# Digital_Port_C_Button.net
KiCad netlist of a schematic drawn in Altium Designer
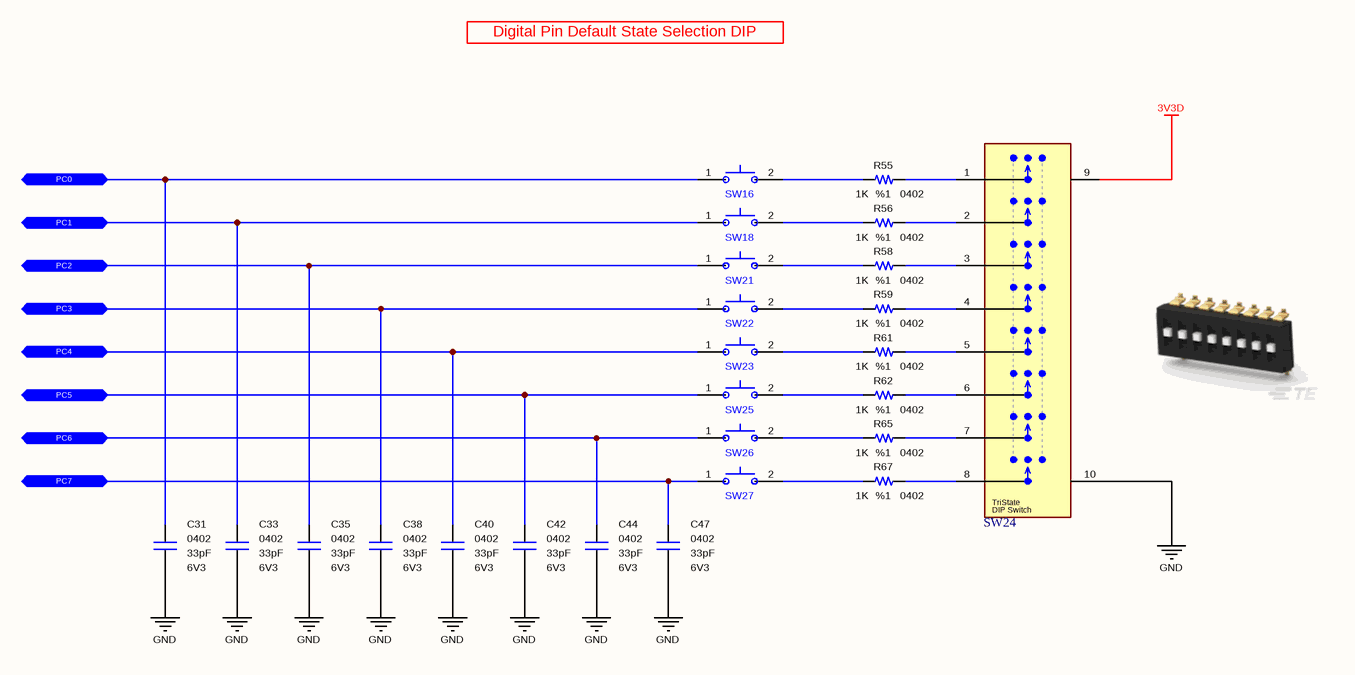
[diagram p0: Digital Port C Button.SchDoc]

(export (version "E")
  (design (tool "Eeschema 10.0.6"))
  (components
    (comp (ref "C31")
      (value "33pF")
      (footprint "CAPACITOR_0402")
      (description "Capacitor - 33pF [0402] (Ceramic)")
      (fields
        (field (name "MANUFACTURER PART NUMBER") "C0402C330J9RACAUTO")
        (field (name "MOUSER PART NUMBER") "80-C0402C330J9RAUTO")
        (field (name "CASE") "0402")
        (field (name "VOLTAGE") "6V3")
      )
      (libsource (lib "Ovoo_Library") (part "Capacitor - 33pF [0402-6V3]"))
    )
    (comp (ref "C33")
      (value "33pF")
      (footprint "CAPACITOR_0402")
      (description "Capacitor - 33pF [0402] (Ceramic)")
      (fields
        (field (name "MANUFACTURER PART NUMBER") "C0402C330J9RACAUTO")
        (field (name "MOUSER PART NUMBER") "80-C0402C330J9RAUTO")
        (field (name "CASE") "0402")
        (field (name "VOLTAGE") "6V3")
      )
      (libsource (lib "Ovoo_Library") (part "Capacitor - 33pF [0402-6V3]"))
    )
    (comp (ref "C35")
      (value "33pF")
      (footprint "CAPACITOR_0402")
      (description "Capacitor - 33pF [0402] (Ceramic)")
      (fields
        (field (name "MANUFACTURER PART NUMBER") "C0402C330J9RACAUTO")
        (field (name "MOUSER PART NUMBER") "80-C0402C330J9RAUTO")
        (field (name "CASE") "0402")
        (field (name "VOLTAGE") "6V3")
      )
      (libsource (lib "Ovoo_Library") (part "Capacitor - 33pF [0402-6V3]"))
    )
    (comp (ref "C38")
      (value "33pF")
      (footprint "CAPACITOR_0402")
      (description "Capacitor - 33pF [0402] (Ceramic)")
      (fields
        (field (name "MANUFACTURER PART NUMBER") "C0402C330J9RACAUTO")
        (field (name "MOUSER PART NUMBER") "80-C0402C330J9RAUTO")
        (field (name "CASE") "0402")
        (field (name "VOLTAGE") "6V3")
      )
      (libsource (lib "Ovoo_Library") (part "Capacitor - 33pF [0402-6V3]"))
    )
    (comp (ref "C40")
      (value "33pF")
      (footprint "CAPACITOR_0402")
      (description "Capacitor - 33pF [0402] (Ceramic)")
      (fields
        (field (name "MANUFACTURER PART NUMBER") "C0402C330J9RACAUTO")
        (field (name "MOUSER PART NUMBER") "80-C0402C330J9RAUTO")
        (field (name "CASE") "0402")
        (field (name "VOLTAGE") "6V3")
      )
      (libsource (lib "Ovoo_Library") (part "Capacitor - 33pF [0402-6V3]"))
    )
    (comp (ref "C42")
      (value "33pF")
      (footprint "CAPACITOR_0402")
      (description "Capacitor - 33pF [0402] (Ceramic)")
      (fields
        (field (name "MANUFACTURER PART NUMBER") "C0402C330J9RACAUTO")
        (field (name "MOUSER PART NUMBER") "80-C0402C330J9RAUTO")
        (field (name "CASE") "0402")
        (field (name "VOLTAGE") "6V3")
      )
      (libsource (lib "Ovoo_Library") (part "Capacitor - 33pF [0402-6V3]"))
    )
    (comp (ref "C44")
      (value "33pF")
      (footprint "CAPACITOR_0402")
      (description "Capacitor - 33pF [0402] (Ceramic)")
      (fields
        (field (name "MANUFACTURER PART NUMBER") "C0402C330J9RACAUTO")
        (field (name "MOUSER PART NUMBER") "80-C0402C330J9RAUTO")
        (field (name "CASE") "0402")
        (field (name "VOLTAGE") "6V3")
      )
      (libsource (lib "Ovoo_Library") (part "Capacitor - 33pF [0402-6V3]"))
    )
    (comp (ref "C47")
      (value "33pF")
      (footprint "CAPACITOR_0402")
      (description "Capacitor - 33pF [0402] (Ceramic)")
      (fields
        (field (name "MANUFACTURER PART NUMBER") "C0402C330J9RACAUTO")
        (field (name "MOUSER PART NUMBER") "80-C0402C330J9RAUTO")
        (field (name "CASE") "0402")
        (field (name "VOLTAGE") "6V3")
      )
      (libsource (lib "Ovoo_Library") (part "Capacitor - 33pF [0402-6V3]"))
    )
    (comp (ref "R55")
      (value "1K")
      (footprint "RESISTOR_0402")
      (description "Thick Film Resistors - SMD 1/16 W 1.0 Kohms 1%")
      (fields
        (field (name "MANUFACTURER PART NUMBER") "CRCW04021K00FKED")
        (field (name "MOUSER PART NUMBER") "71-CRCW0402-1.0K-E3")
        (field (name "TOLERANCE") "%1")
        (field (name "CASE") "0402")
      )
      (libsource (lib "Ovoo_Library") (part "Resistor - 1K"))
    )
    (comp (ref "R56")
      (value "1K")
      (footprint "RESISTOR_0402")
      (description "Thick Film Resistors - SMD 1/16 W 1.0 Kohms 1%")
      (fields
        (field (name "MANUFACTURER PART NUMBER") "CRCW04021K00FKED")
        (field (name "MOUSER PART NUMBER") "71-CRCW0402-1.0K-E3")
        (field (name "TOLERANCE") "%1")
        (field (name "CASE") "0402")
      )
      (libsource (lib "Ovoo_Library") (part "Resistor - 1K"))
    )
    (comp (ref "R58")
      (value "1K")
      (footprint "RESISTOR_0402")
      (description "Thick Film Resistors - SMD 1/16 W 1.0 Kohms 1%")
      (fields
        (field (name "MANUFACTURER PART NUMBER") "CRCW04021K00FKED")
        (field (name "MOUSER PART NUMBER") "71-CRCW0402-1.0K-E3")
        (field (name "TOLERANCE") "%1")
        (field (name "CASE") "0402")
      )
      (libsource (lib "Ovoo_Library") (part "Resistor - 1K"))
    )
    (comp (ref "R59")
      (value "1K")
      (footprint "RESISTOR_0402")
      (description "Thick Film Resistors - SMD 1/16 W 1.0 Kohms 1%")
      (fields
        (field (name "MANUFACTURER PART NUMBER") "CRCW04021K00FKED")
        (field (name "MOUSER PART NUMBER") "71-CRCW0402-1.0K-E3")
        (field (name "TOLERANCE") "%1")
        (field (name "CASE") "0402")
      )
      (libsource (lib "Ovoo_Library") (part "Resistor - 1K"))
    )
    (comp (ref "R61")
      (value "1K")
      (footprint "RESISTOR_0402")
      (description "Thick Film Resistors - SMD 1/16 W 1.0 Kohms 1%")
      (fields
        (field (name "MANUFACTURER PART NUMBER") "CRCW04021K00FKED")
        (field (name "MOUSER PART NUMBER") "71-CRCW0402-1.0K-E3")
        (field (name "TOLERANCE") "%1")
        (field (name "CASE") "0402")
      )
      (libsource (lib "Ovoo_Library") (part "Resistor - 1K"))
    )
    (comp (ref "R62")
      (value "1K")
      (footprint "RESISTOR_0402")
      (description "Thick Film Resistors - SMD 1/16 W 1.0 Kohms 1%")
      (fields
        (field (name "MANUFACTURER PART NUMBER") "CRCW04021K00FKED")
        (field (name "MOUSER PART NUMBER") "71-CRCW0402-1.0K-E3")
        (field (name "TOLERANCE") "%1")
        (field (name "CASE") "0402")
      )
      (libsource (lib "Ovoo_Library") (part "Resistor - 1K"))
    )
    (comp (ref "R65")
      (value "1K")
      (footprint "RESISTOR_0402")
      (description "Thick Film Resistors - SMD 1/16 W 1.0 Kohms 1%")
      (fields
        (field (name "MANUFACTURER PART NUMBER") "CRCW04021K00FKED")
        (field (name "MOUSER PART NUMBER") "71-CRCW0402-1.0K-E3")
        (field (name "TOLERANCE") "%1")
        (field (name "CASE") "0402")
      )
      (libsource (lib "Ovoo_Library") (part "Resistor - 1K"))
    )
    (comp (ref "R67")
      (value "1K")
      (footprint "RESISTOR_0402")
      (description "Thick Film Resistors - SMD 1/16 W 1.0 Kohms 1%")
      (fields
        (field (name "MANUFACTURER PART NUMBER") "CRCW04021K00FKED")
        (field (name "MOUSER PART NUMBER") "71-CRCW0402-1.0K-E3")
        (field (name "TOLERANCE") "%1")
        (field (name "CASE") "0402")
      )
      (libsource (lib "Ovoo_Library") (part "Resistor - 1K"))
    )
    (comp (ref "SW16")
      (value "Tactile Switches")
      (footprint "PTS526_Switch")
      (description "Tactile Switches 50mA 12VDC, 5.2x5.2mm, 0.8mm H, 260gf, G leads.")
      (fields
        (field (name "MANUFACTURER PART NUMBER") "PTS526 SK08 SMTR2 LFS")
        (field (name "MOUSER PART NUMBER") "611-PTS526SK08SMTR2L")
      )
      (libsource (lib "Ovoo_Library") (part "Switch - Tactile"))
    )
    (comp (ref "SW18")
      (value "Tactile Switches")
      (footprint "PTS526_Switch")
      (description "Tactile Switches 50mA 12VDC, 5.2x5.2mm, 0.8mm H, 260gf, G leads.")
      (fields
        (field (name "MANUFACTURER PART NUMBER") "PTS526 SK08 SMTR2 LFS")
        (field (name "MOUSER PART NUMBER") "611-PTS526SK08SMTR2L")
      )
      (libsource (lib "Ovoo_Library") (part "Switch - Tactile"))
    )
    (comp (ref "SW21")
      (value "Tactile Switches")
      (footprint "PTS526_Switch")
      (description "Tactile Switches 50mA 12VDC, 5.2x5.2mm, 0.8mm H, 260gf, G leads.")
      (fields
        (field (name "MANUFACTURER PART NUMBER") "PTS526 SK08 SMTR2 LFS")
        (field (name "MOUSER PART NUMBER") "611-PTS526SK08SMTR2L")
      )
      (libsource (lib "Ovoo_Library") (part "Switch - Tactile"))
    )
    (comp (ref "SW22")
      (value "Tactile Switches")
      (footprint "PTS526_Switch")
      (description "Tactile Switches 50mA 12VDC, 5.2x5.2mm, 0.8mm H, 260gf, G leads.")
      (fields
        (field (name "MANUFACTURER PART NUMBER") "PTS526 SK08 SMTR2 LFS")
        (field (name "MOUSER PART NUMBER") "611-PTS526SK08SMTR2L")
      )
      (libsource (lib "Ovoo_Library") (part "Switch - Tactile"))
    )
    (comp (ref "SW23")
      (value "Tactile Switches")
      (footprint "PTS526_Switch")
      (description "Tactile Switches 50mA 12VDC, 5.2x5.2mm, 0.8mm H, 260gf, G leads.")
      (fields
        (field (name "MANUFACTURER PART NUMBER") "PTS526 SK08 SMTR2 LFS")
        (field (name "MOUSER PART NUMBER") "611-PTS526SK08SMTR2L")
      )
      (libsource (lib "Ovoo_Library") (part "Switch - Tactile"))
    )
    (comp (ref "SW24")
      (value "DIP Switches/SIP Switches")
      (footprint "TDS08SGNNTR04")
      (description "DIP Switches/SIP Switches TRI-STATE DIP 8P G RAISED T&R")
      (fields
        (field (name "MANUFACTURER PART NUMBER") "TDS08SGNNTR04")
        (field (name "MOUSER PART NUMBER") "506-TDS08SGNNTR04")
      )
      (libsource (lib "Ovoo_Library") (part "Switch - DIP Switch (8 Pole TriState)"))
    )
    (comp (ref "SW25")
      (value "Tactile Switches")
      (footprint "PTS526_Switch")
      (description "Tactile Switches 50mA 12VDC, 5.2x5.2mm, 0.8mm H, 260gf, G leads.")
      (fields
        (field (name "MANUFACTURER PART NUMBER") "PTS526 SK08 SMTR2 LFS")
        (field (name "MOUSER PART NUMBER") "611-PTS526SK08SMTR2L")
      )
      (libsource (lib "Ovoo_Library") (part "Switch - Tactile"))
    )
    (comp (ref "SW26")
      (value "Tactile Switches")
      (footprint "PTS526_Switch")
      (description "Tactile Switches 50mA 12VDC, 5.2x5.2mm, 0.8mm H, 260gf, G leads.")
      (fields
        (field (name "MANUFACTURER PART NUMBER") "PTS526 SK08 SMTR2 LFS")
        (field (name "MOUSER PART NUMBER") "611-PTS526SK08SMTR2L")
      )
      (libsource (lib "Ovoo_Library") (part "Switch - Tactile"))
    )
    (comp (ref "SW27")
      (value "Tactile Switches")
      (footprint "PTS526_Switch")
      (description "Tactile Switches 50mA 12VDC, 5.2x5.2mm, 0.8mm H, 260gf, G leads.")
      (fields
        (field (name "MANUFACTURER PART NUMBER") "PTS526 SK08 SMTR2 LFS")
        (field (name "MOUSER PART NUMBER") "611-PTS526SK08SMTR2L")
      )
      (libsource (lib "Ovoo_Library") (part "Switch - Tactile"))
    )
  )
  (nets
    (net (code "1") (name "/PC0") (class "Default")
      (node (ref "C31") (pin "2") (pinfunction "2_2") (pintype "passive"))
      (node (ref "SW16") (pin "1") (pinfunction "NC_1") (pintype "passive"))
    )
    (net (code "2") (name "/PC1") (class "Default")
      (node (ref "C33") (pin "2") (pinfunction "2_2") (pintype "passive"))
      (node (ref "SW18") (pin "1") (pinfunction "NC_1") (pintype "passive"))
    )
    (net (code "3") (name "/PC2") (class "Default")
      (node (ref "C35") (pin "2") (pinfunction "2_2") (pintype "passive"))
      (node (ref "SW21") (pin "1") (pinfunction "NC_1") (pintype "passive"))
    )
    (net (code "4") (name "/PC3") (class "Default")
      (node (ref "C38") (pin "2") (pinfunction "2_2") (pintype "passive"))
      (node (ref "SW22") (pin "1") (pinfunction "NC_1") (pintype "passive"))
    )
    (net (code "5") (name "/PC4") (class "Default")
      (node (ref "C40") (pin "2") (pinfunction "2_2") (pintype "passive"))
      (node (ref "SW23") (pin "1") (pinfunction "NC_1") (pintype "passive"))
    )
    (net (code "6") (name "/PC5") (class "Default")
      (node (ref "C42") (pin "2") (pinfunction "2_2") (pintype "passive"))
      (node (ref "SW25") (pin "1") (pinfunction "NC_1") (pintype "passive"))
    )
    (net (code "7") (name "/PC6") (class "Default")
      (node (ref "C44") (pin "2") (pinfunction "2_2") (pintype "passive"))
      (node (ref "SW26") (pin "1") (pinfunction "NC_1") (pintype "passive"))
    )
    (net (code "8") (name "/PC7") (class "Default")
      (node (ref "C47") (pin "2") (pinfunction "2_2") (pintype "passive"))
      (node (ref "SW27") (pin "1") (pinfunction "NC_1") (pintype "passive"))
    )
    (net (code "9") (name "3V3D") (class "Default")
      (node (ref "SW24") (pin "9") (pinfunction "VCC_9") (pintype "passive"))
    )
    (net (code "10") (name "GND") (class "Default")
      (node (ref "C31") (pin "1") (pinfunction "1_1") (pintype "passive"))
      (node (ref "C33") (pin "1") (pinfunction "1_1") (pintype "passive"))
      (node (ref "C35") (pin "1") (pinfunction "1_1") (pintype "passive"))
      (node (ref "C38") (pin "1") (pinfunction "1_1") (pintype "passive"))
      (node (ref "C40") (pin "1") (pinfunction "1_1") (pintype "passive"))
      (node (ref "C42") (pin "1") (pinfunction "1_1") (pintype "passive"))
      (node (ref "C44") (pin "1") (pinfunction "1_1") (pintype "passive"))
      (node (ref "C47") (pin "1") (pinfunction "1_1") (pintype "passive"))
      (node (ref "SW24") (pin "10") (pinfunction "GND_10") (pintype "passive"))
    )
    (net (code "11") (name "Net-(R55-Pad1)") (class "Default")
      (node (ref "R55") (pin "1") (pinfunction "1_1") (pintype "passive"))
      (node (ref "SW24") (pin "1") (pinfunction "1_1") (pintype "passive"))
    )
    (net (code "12") (name "Net-(R56-Pad1)") (class "Default")
      (node (ref "R56") (pin "1") (pinfunction "1_1") (pintype "passive"))
      (node (ref "SW24") (pin "2") (pinfunction "2_2") (pintype "passive"))
    )
    (net (code "13") (name "Net-(R58-Pad1)") (class "Default")
      (node (ref "R58") (pin "1") (pinfunction "1_1") (pintype "passive"))
      (node (ref "SW24") (pin "3") (pinfunction "3_3") (pintype "passive"))
    )
    (net (code "14") (name "Net-(R59-Pad1)") (class "Default")
      (node (ref "R59") (pin "1") (pinfunction "1_1") (pintype "passive"))
      (node (ref "SW24") (pin "4") (pinfunction "4_4") (pintype "passive"))
    )
    (net (code "15") (name "Net-(R61-Pad1)") (class "Default")
      (node (ref "R61") (pin "1") (pinfunction "1_1") (pintype "passive"))
      (node (ref "SW24") (pin "5") (pinfunction "5_5") (pintype "passive"))
    )
    (net (code "16") (name "Net-(R62-Pad1)") (class "Default")
      (node (ref "R62") (pin "1") (pinfunction "1_1") (pintype "passive"))
      (node (ref "SW24") (pin "6") (pinfunction "6_6") (pintype "passive"))
    )
    (net (code "17") (name "Net-(R65-Pad1)") (class "Default")
      (node (ref "R65") (pin "1") (pinfunction "1_1") (pintype "passive"))
      (node (ref "SW24") (pin "7") (pinfunction "7_7") (pintype "passive"))
    )
    (net (code "18") (name "Net-(R67-Pad1)") (class "Default")
      (node (ref "R67") (pin "1") (pinfunction "1_1") (pintype "passive"))
      (node (ref "SW24") (pin "8") (pinfunction "8_8") (pintype "passive"))
    )
    (net (code "19") (name "Net-(SW16-COM)") (class "Default")
      (node (ref "R55") (pin "2") (pinfunction "2_2") (pintype "passive"))
      (node (ref "SW16") (pin "2") (pinfunction "COM_2") (pintype "passive"))
    )
    (net (code "20") (name "Net-(SW18-COM)") (class "Default")
      (node (ref "R56") (pin "2") (pinfunction "2_2") (pintype "passive"))
      (node (ref "SW18") (pin "2") (pinfunction "COM_2") (pintype "passive"))
    )
    (net (code "21") (name "Net-(SW21-COM)") (class "Default")
      (node (ref "R58") (pin "2") (pinfunction "2_2") (pintype "passive"))
      (node (ref "SW21") (pin "2") (pinfunction "COM_2") (pintype "passive"))
    )
    (net (code "22") (name "Net-(SW22-COM)") (class "Default")
      (node (ref "R59") (pin "2") (pinfunction "2_2") (pintype "passive"))
      (node (ref "SW22") (pin "2") (pinfunction "COM_2") (pintype "passive"))
    )
    (net (code "23") (name "Net-(SW23-COM)") (class "Default")
      (node (ref "R61") (pin "2") (pinfunction "2_2") (pintype "passive"))
      (node (ref "SW23") (pin "2") (pinfunction "COM_2") (pintype "passive"))
    )
    (net (code "24") (name "Net-(SW25-COM)") (class "Default")
      (node (ref "R62") (pin "2") (pinfunction "2_2") (pintype "passive"))
      (node (ref "SW25") (pin "2") (pinfunction "COM_2") (pintype "passive"))
    )
    (net (code "25") (name "Net-(SW26-COM)") (class "Default")
      (node (ref "R65") (pin "2") (pinfunction "2_2") (pintype "passive"))
      (node (ref "SW26") (pin "2") (pinfunction "COM_2") (pintype "passive"))
    )
    (net (code "26") (name "Net-(SW27-COM)") (class "Default")
      (node (ref "R67") (pin "2") (pinfunction "2_2") (pintype "passive"))
      (node (ref "SW27") (pin "2") (pinfunction "COM_2") (pintype "passive"))
    )
  )
)
